# SCH_Club-Vote-Decider_2025-12-05_2.net
KiCad netlist of a schematic drawn in EasyEDA
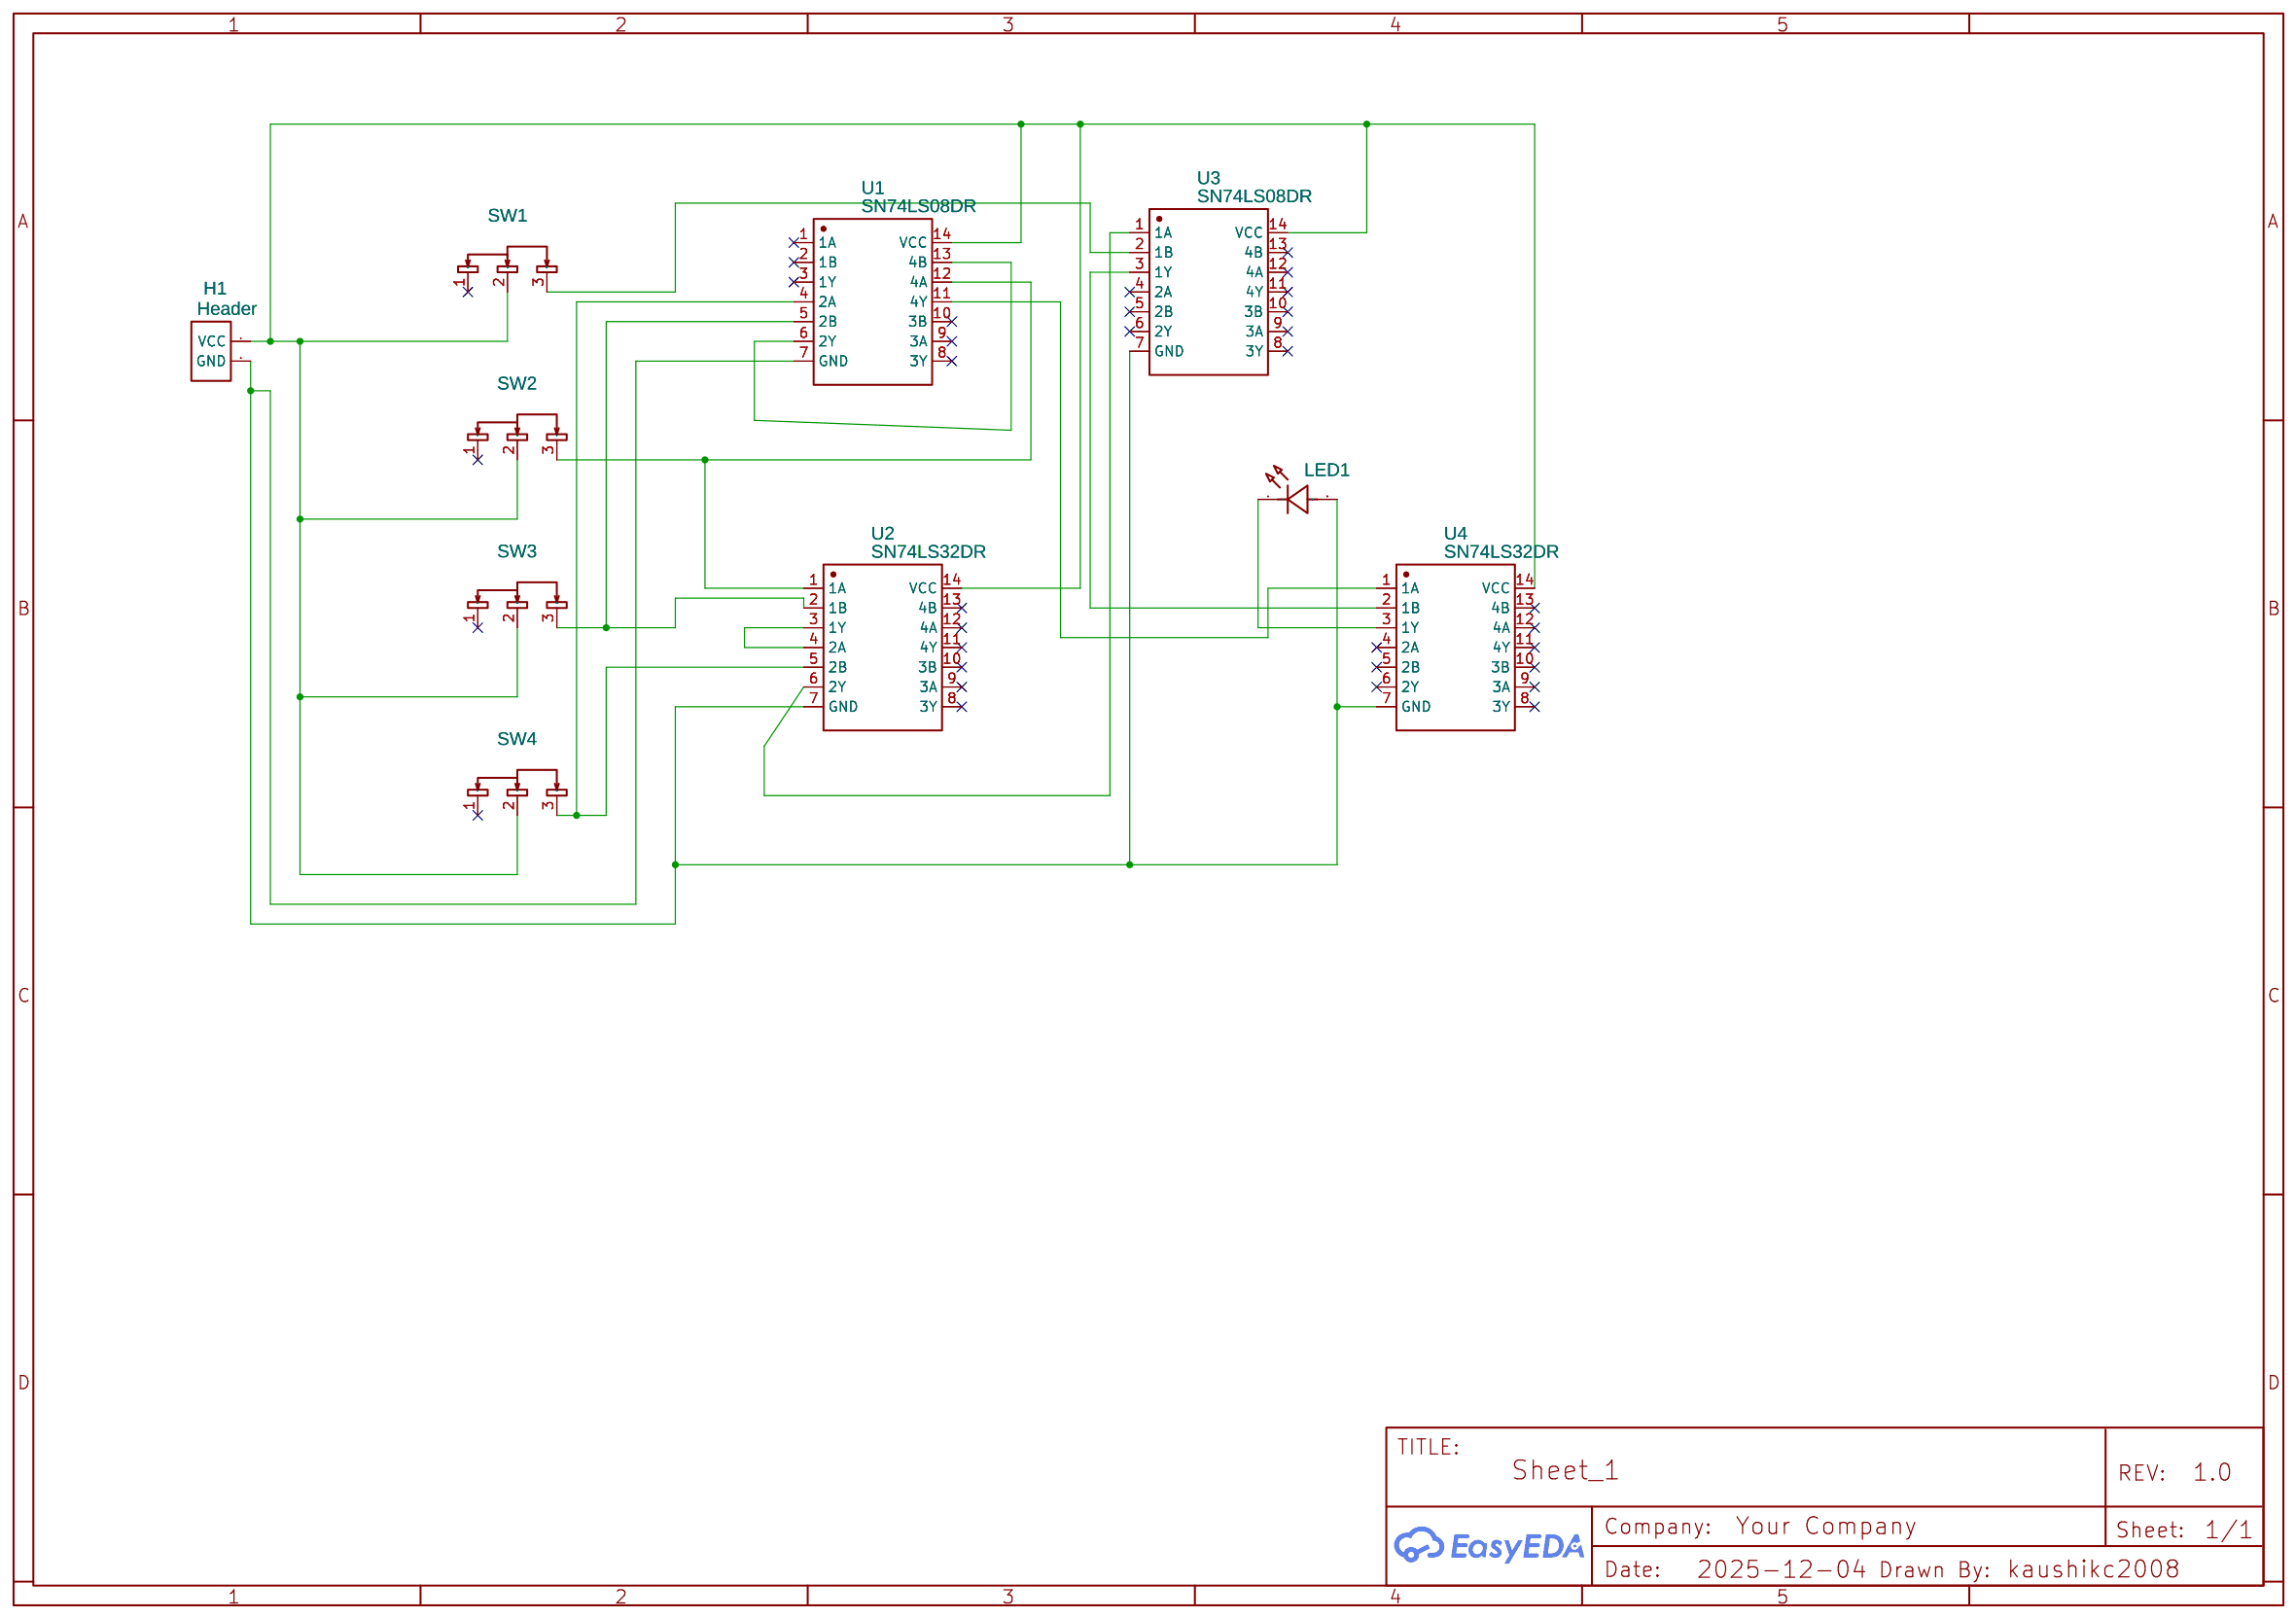
[diagram p0: schematic sheet]

(export (version "E")
  (design (tool "Eeschema 10.0.6"))
  (components
    (comp (ref "H1") (value "Header") (libsource (lib "") (part "HEADER-FEMALE-2.54_1X2")))
    (comp (ref "LED1")
      (value "XL-502UWC")
      (fields (field (name "Manufacturer") "XINGLIGHT(成兴光)"))
      (libsource (lib "") (part "XL-502UWC"))
    )
    (comp (ref "SW1")
      (value "MST-12D18G4 SPDT SLIDE SWITCH")
      (fields
        (field (name "Manufacturer Part") "MST-12D18G4 SPDT Slide Switch")
        (field (name "Manufacturer") "SHOU HAN(首韩)")
      )
      (libsource (lib "") (part "MST-12D18G4 SPDT SLIDE SWITCH"))
    )
    (comp (ref "SW2")
      (value "MST-12D18G4 SPDT SLIDE SWITCH")
      (fields
        (field (name "Manufacturer Part") "MST-12D18G4 SPDT Slide Switch")
        (field (name "Manufacturer") "SHOU HAN(首韩)")
      )
      (libsource (lib "") (part "MST-12D18G4 SPDT SLIDE SWITCH"))
    )
    (comp (ref "SW3")
      (value "MST-12D18G4 SPDT SLIDE SWITCH")
      (fields
        (field (name "Manufacturer Part") "MST-12D18G4 SPDT Slide Switch")
        (field (name "Manufacturer") "SHOU HAN(首韩)")
      )
      (libsource (lib "") (part "MST-12D18G4 SPDT SLIDE SWITCH"))
    )
    (comp (ref "SW4")
      (value "MST-12D18G4 SPDT SLIDE SWITCH")
      (fields
        (field (name "Manufacturer Part") "MST-12D18G4 SPDT Slide Switch")
        (field (name "Manufacturer") "SHOU HAN(首韩)")
      )
      (libsource (lib "") (part "MST-12D18G4 SPDT SLIDE SWITCH"))
    )
    (comp (ref "U1")
      (value "SN74LS08DR")
      (fields (field (name "Manufacturer") "TI(德州仪器)"))
      (libsource (lib "") (part "SN74LS08DR"))
    )
    (comp (ref "U2")
      (value "SN74LS32DR")
      (fields (field (name "Manufacturer") "TI(德州仪器)"))
      (libsource (lib "") (part "SN74LS32DR"))
    )
    (comp (ref "U3")
      (value "SN74LS08DR")
      (fields (field (name "Manufacturer") "TI(德州仪器)"))
      (libsource (lib "") (part "SN74LS08DR"))
    )
    (comp (ref "U4")
      (value "SN74LS32DR")
      (fields (field (name "Manufacturer") "TI(德州仪器)"))
      (libsource (lib "") (part "SN74LS32DR"))
    )
  )
  (nets
    (net (code "1") (name "Net-(H1-GND)") (class "Default")
      (node (ref "H1") (pin "2") (pinfunction "GND_2") (pintype "unspecified"))
      (node (ref "LED1") (pin "2") (pinfunction "A_2") (pintype "unspecified"))
      (node (ref "U1") (pin "7") (pinfunction "GND_7") (pintype "unspecified"))
      (node (ref "U2") (pin "7") (pinfunction "GND_7") (pintype "unspecified"))
      (node (ref "U3") (pin "7") (pinfunction "GND_7") (pintype "unspecified"))
      (node (ref "U4") (pin "7") (pinfunction "GND_7") (pintype "unspecified"))
    )
    (net (code "2") (name "Net-(H1-VCC)") (class "Default")
      (node (ref "H1") (pin "1") (pinfunction "VCC_1") (pintype "unspecified"))
      (node (ref "SW1") (pin "2") (pinfunction "2_2") (pintype "unspecified"))
      (node (ref "SW2") (pin "2") (pinfunction "2_2") (pintype "unspecified"))
      (node (ref "SW3") (pin "2") (pinfunction "2_2") (pintype "unspecified"))
      (node (ref "SW4") (pin "2") (pinfunction "2_2") (pintype "unspecified"))
      (node (ref "U1") (pin "14") (pinfunction "VCC_14") (pintype "unspecified"))
      (node (ref "U2") (pin "14") (pinfunction "VCC_14") (pintype "unspecified"))
      (node (ref "U3") (pin "14") (pinfunction "VCC_14") (pintype "unspecified"))
      (node (ref "U4") (pin "14") (pinfunction "VCC_14") (pintype "unspecified"))
    )
    (net (code "3") (name "Net-(LED1-K)") (class "Default")
      (node (ref "LED1") (pin "1") (pinfunction "K_1") (pintype "unspecified"))
      (node (ref "U4") (pin "3") (pinfunction "1Y_3") (pintype "unspecified"))
    )
    (net (code "4") (name "Net-(U1-2A)") (class "Default")
      (node (ref "SW4") (pin "3") (pinfunction "3_3") (pintype "unspecified"))
      (node (ref "U1") (pin "4") (pinfunction "2A_4") (pintype "unspecified"))
      (node (ref "U2") (pin "5") (pinfunction "2B_5") (pintype "unspecified"))
    )
    (net (code "5") (name "Net-(U1-2B)") (class "Default")
      (node (ref "SW3") (pin "3") (pinfunction "3_3") (pintype "unspecified"))
      (node (ref "U1") (pin "5") (pinfunction "2B_5") (pintype "unspecified"))
      (node (ref "U2") (pin "2") (pinfunction "1B_2") (pintype "unspecified"))
    )
    (net (code "6") (name "Net-(U1-2Y)") (class "Default")
      (node (ref "U1") (pin "13") (pinfunction "4B_13") (pintype "unspecified"))
      (node (ref "U1") (pin "6") (pinfunction "2Y_6") (pintype "unspecified"))
    )
    (net (code "7") (name "Net-(U1-4A)") (class "Default")
      (node (ref "SW2") (pin "3") (pinfunction "3_3") (pintype "unspecified"))
      (node (ref "U1") (pin "12") (pinfunction "4A_12") (pintype "unspecified"))
      (node (ref "U2") (pin "1") (pinfunction "1A_1") (pintype "unspecified"))
    )
    (net (code "8") (name "Net-(U1-4Y)") (class "Default")
      (node (ref "U1") (pin "11") (pinfunction "4Y_11") (pintype "unspecified"))
      (node (ref "U4") (pin "1") (pinfunction "1A_1") (pintype "unspecified"))
    )
    (net (code "9") (name "Net-(U2-1Y)") (class "Default")
      (node (ref "U2") (pin "3") (pinfunction "1Y_3") (pintype "unspecified"))
      (node (ref "U2") (pin "4") (pinfunction "2A_4") (pintype "unspecified"))
    )
    (net (code "10") (name "Net-(U2-2Y)") (class "Default")
      (node (ref "U2") (pin "6") (pinfunction "2Y_6") (pintype "unspecified"))
      (node (ref "U3") (pin "1") (pinfunction "1A_1") (pintype "unspecified"))
    )
    (net (code "11") (name "Net-(U3-1B)") (class "Default")
      (node (ref "SW1") (pin "3") (pinfunction "3_3") (pintype "unspecified"))
      (node (ref "U3") (pin "2") (pinfunction "1B_2") (pintype "unspecified"))
    )
    (net (code "12") (name "Net-(U3-1Y)") (class "Default")
      (node (ref "U3") (pin "3") (pinfunction "1Y_3") (pintype "unspecified"))
      (node (ref "U4") (pin "2") (pinfunction "1B_2") (pintype "unspecified"))
    )
    (net (code "13") (name "unconnected-(SW1-Pad1)") (class "Default")
      (node (ref "SW1") (pin "1") (pinfunction "1_1") (pintype "unspecified+no_connect"))
    )
    (net (code "14") (name "unconnected-(SW2-Pad1)") (class "Default")
      (node (ref "SW2") (pin "1") (pinfunction "1_1") (pintype "unspecified+no_connect"))
    )
    (net (code "15") (name "unconnected-(SW3-Pad1)") (class "Default")
      (node (ref "SW3") (pin "1") (pinfunction "1_1") (pintype "unspecified+no_connect"))
    )
    (net (code "16") (name "unconnected-(SW4-Pad1)") (class "Default")
      (node (ref "SW4") (pin "1") (pinfunction "1_1") (pintype "unspecified+no_connect"))
    )
    (net (code "17") (name "unconnected-(U1-1A-Pad1)") (class "Default")
      (node (ref "U1") (pin "1") (pinfunction "1A_1") (pintype "unspecified+no_connect"))
    )
    (net (code "18") (name "unconnected-(U1-1B-Pad2)") (class "Default")
      (node (ref "U1") (pin "2") (pinfunction "1B_2") (pintype "unspecified+no_connect"))
    )
    (net (code "19") (name "unconnected-(U1-1Y-Pad3)") (class "Default")
      (node (ref "U1") (pin "3") (pinfunction "1Y_3") (pintype "unspecified+no_connect"))
    )
    (net (code "20") (name "unconnected-(U1-3A-Pad9)") (class "Default")
      (node (ref "U1") (pin "9") (pinfunction "3A_9") (pintype "unspecified+no_connect"))
    )
    (net (code "21") (name "unconnected-(U1-3B-Pad10)") (class "Default")
      (node (ref "U1") (pin "10") (pinfunction "3B_10") (pintype "unspecified+no_connect"))
    )
    (net (code "22") (name "unconnected-(U1-3Y-Pad8)") (class "Default")
      (node (ref "U1") (pin "8") (pinfunction "3Y_8") (pintype "unspecified+no_connect"))
    )
    (net (code "23") (name "unconnected-(U2-3A-Pad9)") (class "Default")
      (node (ref "U2") (pin "9") (pinfunction "3A_9") (pintype "unspecified+no_connect"))
    )
    (net (code "24") (name "unconnected-(U2-3B-Pad10)") (class "Default")
      (node (ref "U2") (pin "10") (pinfunction "3B_10") (pintype "unspecified+no_connect"))
    )
    (net (code "25") (name "unconnected-(U2-3Y-Pad8)") (class "Default")
      (node (ref "U2") (pin "8") (pinfunction "3Y_8") (pintype "unspecified+no_connect"))
    )
    (net (code "26") (name "unconnected-(U2-4A-Pad12)") (class "Default")
      (node (ref "U2") (pin "12") (pinfunction "4A_12") (pintype "unspecified+no_connect"))
    )
    (net (code "27") (name "unconnected-(U2-4B-Pad13)") (class "Default")
      (node (ref "U2") (pin "13") (pinfunction "4B_13") (pintype "unspecified+no_connect"))
    )
    (net (code "28") (name "unconnected-(U2-4Y-Pad11)") (class "Default")
      (node (ref "U2") (pin "11") (pinfunction "4Y_11") (pintype "unspecified+no_connect"))
    )
    (net (code "29") (name "unconnected-(U3-2A-Pad4)") (class "Default")
      (node (ref "U3") (pin "4") (pinfunction "2A_4") (pintype "unspecified+no_connect"))
    )
    (net (code "30") (name "unconnected-(U3-2B-Pad5)") (class "Default")
      (node (ref "U3") (pin "5") (pinfunction "2B_5") (pintype "unspecified+no_connect"))
    )
    (net (code "31") (name "unconnected-(U3-2Y-Pad6)") (class "Default")
      (node (ref "U3") (pin "6") (pinfunction "2Y_6") (pintype "unspecified+no_connect"))
    )
    (net (code "32") (name "unconnected-(U3-3A-Pad9)") (class "Default")
      (node (ref "U3") (pin "9") (pinfunction "3A_9") (pintype "unspecified+no_connect"))
    )
    (net (code "33") (name "unconnected-(U3-3B-Pad10)") (class "Default")
      (node (ref "U3") (pin "10") (pinfunction "3B_10") (pintype "unspecified+no_connect"))
    )
    (net (code "34") (name "unconnected-(U3-3Y-Pad8)") (class "Default")
      (node (ref "U3") (pin "8") (pinfunction "3Y_8") (pintype "unspecified+no_connect"))
    )
    (net (code "35") (name "unconnected-(U3-4A-Pad12)") (class "Default")
      (node (ref "U3") (pin "12") (pinfunction "4A_12") (pintype "unspecified+no_connect"))
    )
    (net (code "36") (name "unconnected-(U3-4B-Pad13)") (class "Default")
      (node (ref "U3") (pin "13") (pinfunction "4B_13") (pintype "unspecified+no_connect"))
    )
    (net (code "37") (name "unconnected-(U3-4Y-Pad11)") (class "Default")
      (node (ref "U3") (pin "11") (pinfunction "4Y_11") (pintype "unspecified+no_connect"))
    )
    (net (code "38") (name "unconnected-(U4-2A-Pad4)") (class "Default")
      (node (ref "U4") (pin "4") (pinfunction "2A_4") (pintype "unspecified+no_connect"))
    )
    (net (code "39") (name "unconnected-(U4-2B-Pad5)") (class "Default")
      (node (ref "U4") (pin "5") (pinfunction "2B_5") (pintype "unspecified+no_connect"))
    )
    (net (code "40") (name "unconnected-(U4-2Y-Pad6)") (class "Default")
      (node (ref "U4") (pin "6") (pinfunction "2Y_6") (pintype "unspecified+no_connect"))
    )
    (net (code "41") (name "unconnected-(U4-3A-Pad9)") (class "Default")
      (node (ref "U4") (pin "9") (pinfunction "3A_9") (pintype "unspecified+no_connect"))
    )
    (net (code "42") (name "unconnected-(U4-3B-Pad10)") (class "Default")
      (node (ref "U4") (pin "10") (pinfunction "3B_10") (pintype "unspecified+no_connect"))
    )
    (net (code "43") (name "unconnected-(U4-3Y-Pad8)") (class "Default")
      (node (ref "U4") (pin "8") (pinfunction "3Y_8") (pintype "unspecified+no_connect"))
    )
    (net (code "44") (name "unconnected-(U4-4A-Pad12)") (class "Default")
      (node (ref "U4") (pin "12") (pinfunction "4A_12") (pintype "unspecified+no_connect"))
    )
    (net (code "45") (name "unconnected-(U4-4B-Pad13)") (class "Default")
      (node (ref "U4") (pin "13") (pinfunction "4B_13") (pintype "unspecified+no_connect"))
    )
    (net (code "46") (name "unconnected-(U4-4Y-Pad11)") (class "Default")
      (node (ref "U4") (pin "11") (pinfunction "4Y_11") (pintype "unspecified+no_connect"))
    )
  )
)
